# Adafruit_2_2in_TFT_HAT_rev_B.net
KiCad netlist of a schematic drawn in EAGLE
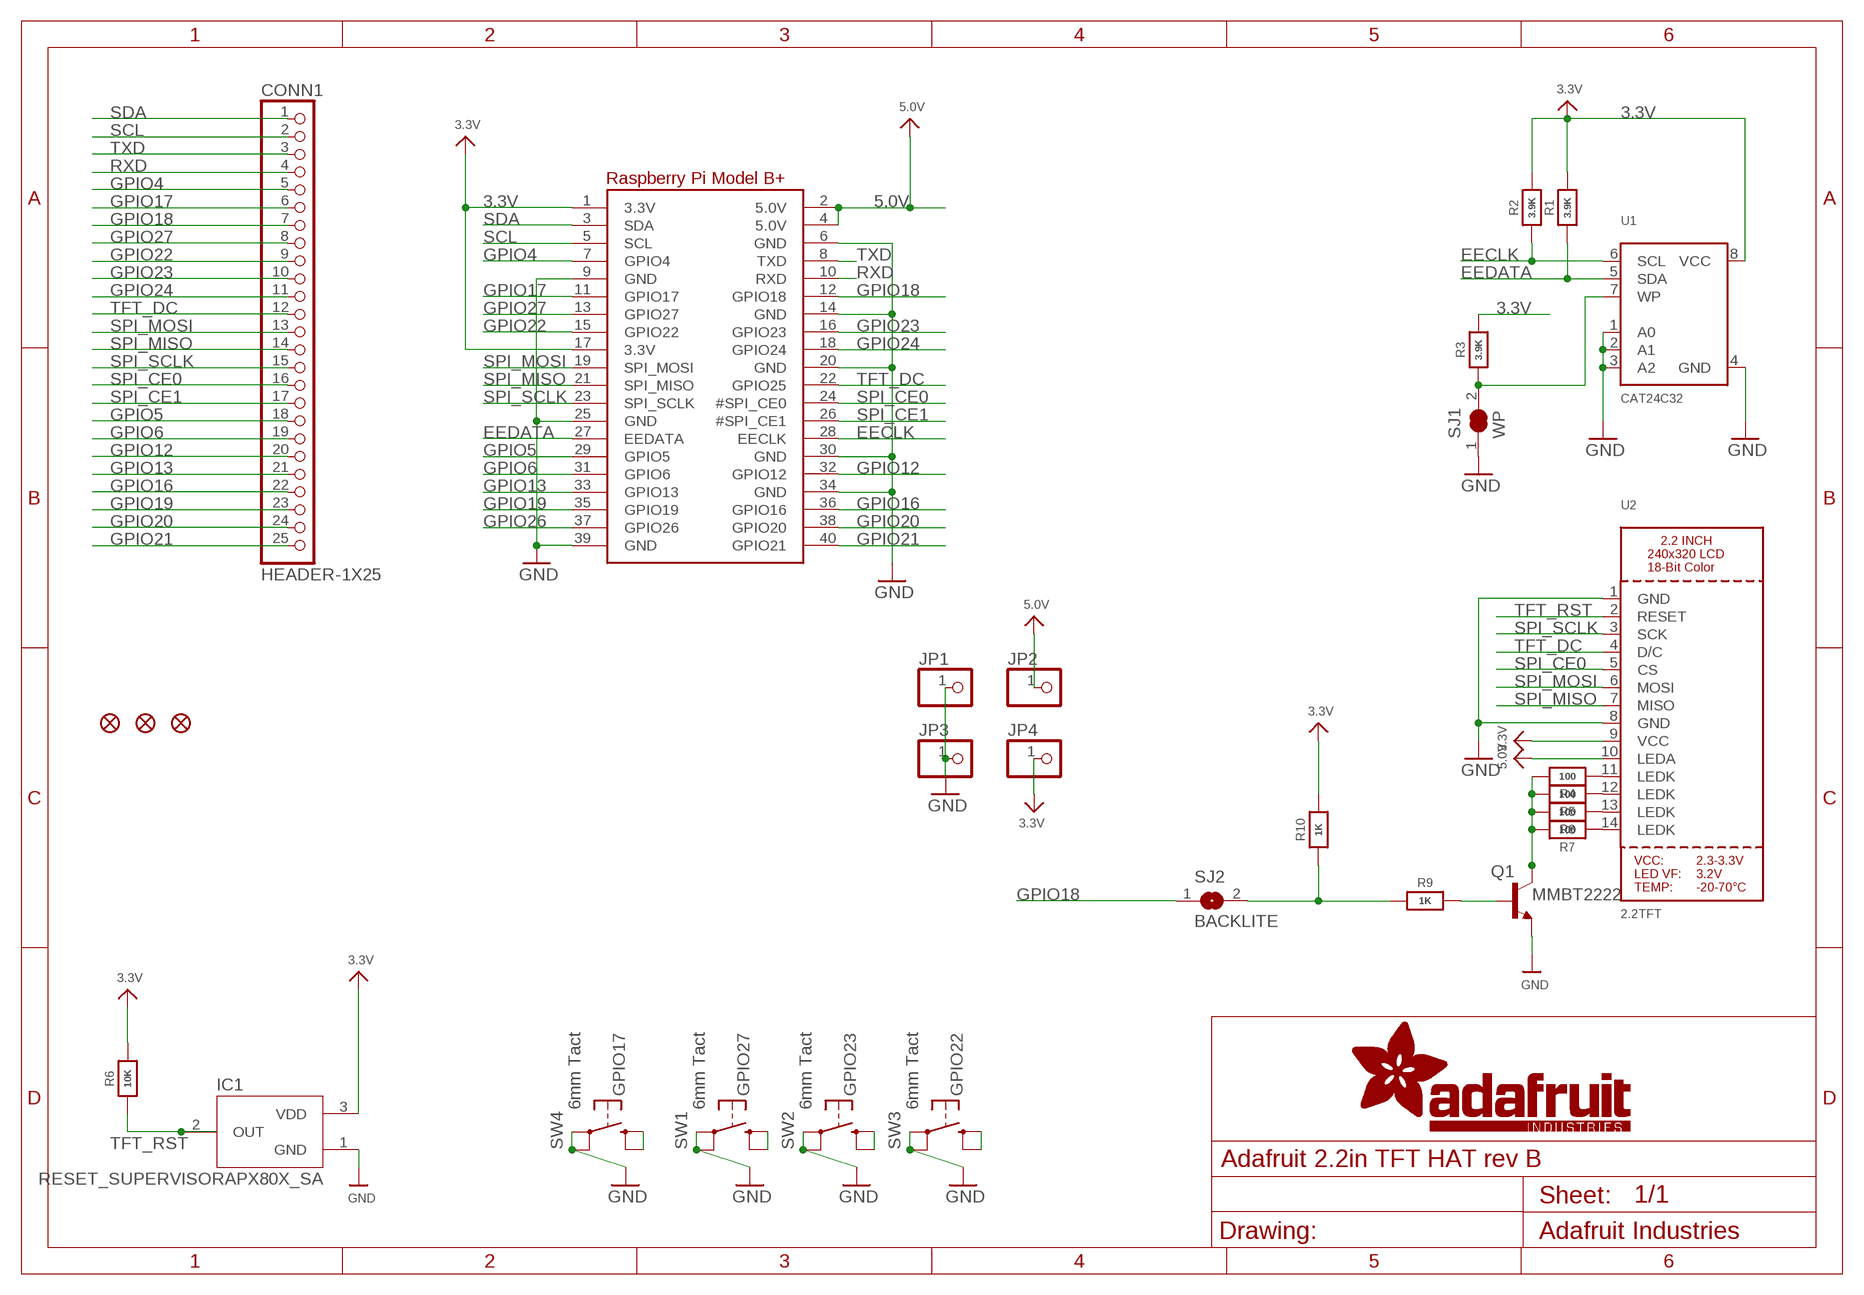
[diagram p0: schematic, sheet 1]

(export (version "E")
  (design (tool "Eeschema 10.0.6"))
  (components
    (comp (ref "CONN1")
      (value "HEADER-1X25")
      (footprint "eagle-import:1X25_ROUND_70MIL")
      (libsource (lib "eagle-import") (part "HEADER-1X25"))
    )
    (comp (ref "FID1")
      (value "FIDUCIAL_1MM")
      (footprint "eagle-import:FIDUCIAL_1MM")
      (libsource (lib "eagle-import") (part "FIDUCIAL_1MM"))
    )
    (comp (ref "FID2")
      (value "FIDUCIAL_1MM")
      (footprint "eagle-import:FIDUCIAL_1MM")
      (libsource (lib "eagle-import") (part "FIDUCIAL_1MM"))
    )
    (comp (ref "FID3")
      (value "FIDUCIAL_1MM")
      (footprint "eagle-import:FIDUCIAL_1MM")
      (libsource (lib "eagle-import") (part "FIDUCIAL_1MM"))
    )
    (comp (ref "IC1")
      (value "RESET_SUPERVISORAPX80X_SA")
      (footprint "eagle-import:SOT23-WIDE")
      (libsource (lib "eagle-import") (part "RESET_SUPERVISORAPX80X_SA"))
    )
    (comp (ref "JP1")
      (value "HEADER-1X1ROUND")
      (footprint "eagle-import:1X01_ROUND")
      (libsource (lib "eagle-import") (part "HEADER-1X1ROUND"))
    )
    (comp (ref "JP2")
      (value "HEADER-1X1ROUND")
      (footprint "eagle-import:1X01_ROUND")
      (libsource (lib "eagle-import") (part "HEADER-1X1ROUND"))
    )
    (comp (ref "JP3")
      (value "HEADER-1X1ROUND")
      (footprint "eagle-import:1X01_ROUND")
      (libsource (lib "eagle-import") (part "HEADER-1X1ROUND"))
    )
    (comp (ref "JP4")
      (value "HEADER-1X1ROUND")
      (footprint "eagle-import:1X01_ROUND")
      (libsource (lib "eagle-import") (part "HEADER-1X1ROUND"))
    )
    (comp (ref "Q1")
      (value "MMBT2222")
      (footprint "eagle-import:SOT23-BEC")
      (libsource (lib "eagle-import") (part "-NPN-SOT23-BECMMBT2222ALT1"))
    )
    (comp (ref "R1")
      (value "3.9K")
      (footprint "eagle-import:0805-NO")
      (libsource (lib "eagle-import") (part "RESISTOR0805_NOOUTLINE"))
    )
    (comp (ref "R2")
      (value "3.9K")
      (footprint "eagle-import:0805-NO")
      (libsource (lib "eagle-import") (part "RESISTOR0805_NOOUTLINE"))
    )
    (comp (ref "R3")
      (value "3.9K")
      (footprint "eagle-import:0805-NO")
      (libsource (lib "eagle-import") (part "RESISTOR0805_NOOUTLINE"))
    )
    (comp (ref "R4")
      (value "100")
      (footprint "eagle-import:0805-NO")
      (libsource (lib "eagle-import") (part "RESISTOR0805_NOOUTLINE"))
    )
    (comp (ref "R5")
      (value "100")
      (footprint "eagle-import:0805-NO")
      (libsource (lib "eagle-import") (part "RESISTOR0805_NOOUTLINE"))
    )
    (comp (ref "R6")
      (value "10K")
      (footprint "eagle-import:0805-NO")
      (libsource (lib "eagle-import") (part "RESISTOR0805_NOOUTLINE"))
    )
    (comp (ref "R7")
      (value "100")
      (footprint "eagle-import:0805-NO")
      (libsource (lib "eagle-import") (part "RESISTOR0805_NOOUTLINE"))
    )
    (comp (ref "R8")
      (value "100")
      (footprint "eagle-import:0805-NO")
      (libsource (lib "eagle-import") (part "RESISTOR0805_NOOUTLINE"))
    )
    (comp (ref "R9")
      (value "1K")
      (footprint "eagle-import:0805-NO")
      (libsource (lib "eagle-import") (part "RESISTOR0805_NOOUTLINE"))
    )
    (comp (ref "R10")
      (value "1K")
      (footprint "eagle-import:0805-NO")
      (libsource (lib "eagle-import") (part "RESISTOR0805_NOOUTLINE"))
    )
    (comp (ref "RPI1")
      (value "RASPBERRYPI_BPLUS_HATNODIM")
      (footprint "eagle-import:PI_HAT_NODIM")
      (libsource (lib "eagle-import") (part "RASPBERRYPI_BPLUS_HATNODIM"))
    )
    (comp (ref "SJ1")
      (value "WP")
      (footprint "eagle-import:SOLDERJUMPER_CLOSEDWIRE")
      (libsource (lib "eagle-import") (part "SOLDERJUMPER_CLOSED"))
    )
    (comp (ref "SJ2")
      (value "BACKLITE")
      (footprint "eagle-import:SOLDERJUMPER_CLOSEDWIRE")
      (libsource (lib "eagle-import") (part "SOLDERJUMPERCLOSED"))
    )
    (comp (ref "SW1")
      (value "6mm Tact")
      (footprint "eagle-import:EVQ-Q2")
      (libsource (lib "eagle-import") (part "SWITCH_TACT_SMT"))
    )
    (comp (ref "SW2")
      (value "6mm Tact")
      (footprint "eagle-import:EVQ-Q2")
      (libsource (lib "eagle-import") (part "SWITCH_TACT_SMT"))
    )
    (comp (ref "SW3")
      (value "6mm Tact")
      (footprint "eagle-import:EVQ-Q2")
      (libsource (lib "eagle-import") (part "SWITCH_TACT_SMT"))
    )
    (comp (ref "SW4")
      (value "6mm Tact")
      (footprint "eagle-import:EVQ-Q2")
      (libsource (lib "eagle-import") (part "SWITCH_TACT_SMT"))
    )
    (comp (ref "U1")
      (value "CAT24C32")
      (footprint "eagle-import:SOIC8_150MIL")
      (libsource (lib "eagle-import") (part "EEPROM_I2C_8PIN_GENERIC"))
    )
    (comp (ref "U2")
      (value "2.2TFT")
      (footprint "eagle-import:TM022HDH26_2.2IN_LCD")
      (libsource (lib "eagle-import") (part "DISP_LCD_TM022HDH26"))
    )
  )
  (nets
    (net (code "1") (name "/EECLK") (class "Default")
      (node (ref "R2") (pin "1") (pinfunction "1_1") (pintype "passive"))
      (node (ref "RPI1") (pin "28") (pinfunction "EECLK_28") (pintype "bidirectional"))
      (node (ref "U1") (pin "6") (pinfunction "SCL_6") (pintype "input"))
    )
    (net (code "2") (name "/EEDATA") (class "Default")
      (node (ref "R1") (pin "1") (pinfunction "1_1") (pintype "passive"))
      (node (ref "RPI1") (pin "27") (pinfunction "EEDATA_27") (pintype "bidirectional"))
      (node (ref "U1") (pin "5") (pinfunction "SDA_5") (pintype "bidirectional"))
    )
    (net (code "3") (name "/GPIO4") (class "Default")
      (node (ref "CONN1") (pin "5") (pinfunction "5_5") (pintype "passive"))
      (node (ref "RPI1") (pin "7") (pinfunction "GPIO4_7") (pintype "bidirectional"))
    )
    (net (code "4") (name "/GPIO5") (class "Default")
      (node (ref "CONN1") (pin "18") (pinfunction "18_18") (pintype "passive"))
      (node (ref "RPI1") (pin "29") (pinfunction "GPIO5_29") (pintype "bidirectional"))
    )
    (net (code "5") (name "/GPIO6") (class "Default")
      (node (ref "CONN1") (pin "19") (pinfunction "19_19") (pintype "passive"))
      (node (ref "RPI1") (pin "31") (pinfunction "GPIO6_31") (pintype "bidirectional"))
    )
    (net (code "6") (name "/GPIO12") (class "Default")
      (node (ref "CONN1") (pin "20") (pinfunction "20_20") (pintype "passive"))
      (node (ref "RPI1") (pin "32") (pinfunction "GPIO12_32") (pintype "bidirectional"))
    )
    (net (code "7") (name "/GPIO13") (class "Default")
      (node (ref "CONN1") (pin "21") (pinfunction "21_21") (pintype "passive"))
      (node (ref "RPI1") (pin "33") (pinfunction "GPIO13_33") (pintype "bidirectional"))
    )
    (net (code "8") (name "/GPIO16") (class "Default")
      (node (ref "CONN1") (pin "22") (pinfunction "22_22") (pintype "passive"))
      (node (ref "RPI1") (pin "36") (pinfunction "GPIO16_36") (pintype "bidirectional"))
    )
    (net (code "9") (name "/GPIO17") (class "Default")
      (node (ref "CONN1") (pin "6") (pinfunction "6_6") (pintype "passive"))
      (node (ref "RPI1") (pin "11") (pinfunction "GPIO17_11") (pintype "bidirectional"))
      (node (ref "SW4") (pin "B") (pinfunction "S_B") (pintype "passive"))
      (node (ref "SW4") (pin "B'") (pinfunction "S1_B'") (pintype "passive"))
    )
    (net (code "10") (name "/GPIO18") (class "Default")
      (node (ref "CONN1") (pin "7") (pinfunction "7_7") (pintype "passive"))
      (node (ref "RPI1") (pin "12") (pinfunction "GPIO18_12") (pintype "bidirectional"))
      (node (ref "SJ2") (pin "1") (pinfunction "1_1") (pintype "passive"))
    )
    (net (code "11") (name "/GPIO19") (class "Default")
      (node (ref "CONN1") (pin "23") (pinfunction "23_23") (pintype "passive"))
      (node (ref "RPI1") (pin "35") (pinfunction "GPIO19_35") (pintype "bidirectional"))
    )
    (net (code "12") (name "/GPIO20") (class "Default")
      (node (ref "CONN1") (pin "24") (pinfunction "24_24") (pintype "passive"))
      (node (ref "RPI1") (pin "38") (pinfunction "GPIO20_38") (pintype "bidirectional"))
    )
    (net (code "13") (name "/GPIO21") (class "Default")
      (node (ref "CONN1") (pin "25") (pinfunction "25_25") (pintype "passive"))
      (node (ref "RPI1") (pin "40") (pinfunction "GPIO21_40") (pintype "bidirectional"))
    )
    (net (code "14") (name "/GPIO22") (class "Default")
      (node (ref "CONN1") (pin "9") (pinfunction "9_9") (pintype "passive"))
      (node (ref "RPI1") (pin "15") (pinfunction "GPIO22_15") (pintype "bidirectional"))
      (node (ref "SW3") (pin "B") (pinfunction "S_B") (pintype "passive"))
      (node (ref "SW3") (pin "B'") (pinfunction "S1_B'") (pintype "passive"))
    )
    (net (code "15") (name "/GPIO23") (class "Default")
      (node (ref "CONN1") (pin "10") (pinfunction "10_10") (pintype "passive"))
      (node (ref "RPI1") (pin "16") (pinfunction "GPIO23_16") (pintype "bidirectional"))
      (node (ref "SW2") (pin "B") (pinfunction "S_B") (pintype "passive"))
      (node (ref "SW2") (pin "B'") (pinfunction "S1_B'") (pintype "passive"))
    )
    (net (code "16") (name "/GPIO24") (class "Default")
      (node (ref "CONN1") (pin "11") (pinfunction "11_11") (pintype "passive"))
      (node (ref "RPI1") (pin "18") (pinfunction "GPIO24_18") (pintype "bidirectional"))
    )
    (net (code "17") (name "/GPIO26") (class "Default")
      (node (ref "RPI1") (pin "37") (pinfunction "GPIO26_37") (pintype "bidirectional"))
    )
    (net (code "18") (name "/GPIO27") (class "Default")
      (node (ref "CONN1") (pin "8") (pinfunction "8_8") (pintype "passive"))
      (node (ref "RPI1") (pin "13") (pinfunction "GPIO27_13") (pintype "bidirectional"))
      (node (ref "SW1") (pin "B") (pinfunction "S_B") (pintype "passive"))
      (node (ref "SW1") (pin "B'") (pinfunction "S1_B'") (pintype "passive"))
    )
    (net (code "19") (name "/RXD") (class "Default")
      (node (ref "CONN1") (pin "4") (pinfunction "4_4") (pintype "passive"))
      (node (ref "RPI1") (pin "10") (pinfunction "RXD_10") (pintype "bidirectional"))
    )
    (net (code "20") (name "/SCL") (class "Default")
      (node (ref "CONN1") (pin "2") (pinfunction "2_2") (pintype "passive"))
      (node (ref "RPI1") (pin "5") (pinfunction "SCL_5") (pintype "bidirectional"))
    )
    (net (code "21") (name "/SDA") (class "Default")
      (node (ref "CONN1") (pin "1") (pinfunction "1_1") (pintype "passive"))
      (node (ref "RPI1") (pin "3") (pinfunction "SDA_3") (pintype "bidirectional"))
    )
    (net (code "22") (name "/SPI_CE0") (class "Default")
      (node (ref "CONN1") (pin "16") (pinfunction "16_16") (pintype "passive"))
      (node (ref "RPI1") (pin "24") (pinfunction "#SPI_CE0_24") (pintype "bidirectional"))
      (node (ref "U2") (pin "5") (pinfunction "CS_5") (pintype "input"))
    )
    (net (code "23") (name "/SPI_CE1") (class "Default")
      (node (ref "CONN1") (pin "17") (pinfunction "17_17") (pintype "passive"))
      (node (ref "RPI1") (pin "26") (pinfunction "#SPI_CE1_26") (pintype "bidirectional"))
    )
    (net (code "24") (name "/SPI_MISO") (class "Default")
      (node (ref "CONN1") (pin "14") (pinfunction "14_14") (pintype "passive"))
      (node (ref "RPI1") (pin "21") (pinfunction "SPI_MISO_21") (pintype "bidirectional"))
      (node (ref "U2") (pin "7") (pinfunction "MISO_7") (pintype "output"))
    )
    (net (code "25") (name "/SPI_MOSI") (class "Default")
      (node (ref "CONN1") (pin "13") (pinfunction "13_13") (pintype "passive"))
      (node (ref "RPI1") (pin "19") (pinfunction "SPI_MOSI_19") (pintype "bidirectional"))
      (node (ref "U2") (pin "6") (pinfunction "MOSI_6") (pintype "input"))
    )
    (net (code "26") (name "/SPI_SCLK") (class "Default")
      (node (ref "CONN1") (pin "15") (pinfunction "15_15") (pintype "passive"))
      (node (ref "RPI1") (pin "23") (pinfunction "SPI_SCLK_23") (pintype "bidirectional"))
      (node (ref "U2") (pin "3") (pinfunction "SCK_3") (pintype "input"))
    )
    (net (code "27") (name "/TFT_DC") (class "Default")
      (node (ref "CONN1") (pin "12") (pinfunction "12_12") (pintype "passive"))
      (node (ref "RPI1") (pin "22") (pinfunction "GPIO25_22") (pintype "bidirectional"))
      (node (ref "U2") (pin "4") (pinfunction "D/C_4") (pintype "input"))
    )
    (net (code "28") (name "/TFT_RST") (class "Default")
      (node (ref "IC1") (pin "2") (pinfunction "OUT_2") (pintype "output"))
      (node (ref "R6") (pin "1") (pinfunction "1_1") (pintype "passive"))
      (node (ref "U2") (pin "2") (pinfunction "RESET_2") (pintype "input"))
    )
    (net (code "29") (name "/TXD") (class "Default")
      (node (ref "CONN1") (pin "3") (pinfunction "3_3") (pintype "passive"))
      (node (ref "RPI1") (pin "8") (pinfunction "TXD_8") (pintype "bidirectional"))
    )
    (net (code "30") (name "3.3V") (class "Default")
      (node (ref "IC1") (pin "3") (pinfunction "VDD_3") (pintype "power_in"))
      (node (ref "JP4") (pin "1") (pinfunction "1_1") (pintype "passive"))
      (node (ref "R1") (pin "2") (pinfunction "2_2") (pintype "passive"))
      (node (ref "R10") (pin "2") (pinfunction "2_2") (pintype "passive"))
      (node (ref "R2") (pin "2") (pinfunction "2_2") (pintype "passive"))
      (node (ref "R3") (pin "2") (pinfunction "2_2") (pintype "passive"))
      (node (ref "R6") (pin "2") (pinfunction "2_2") (pintype "passive"))
      (node (ref "RPI1") (pin "1") (pinfunction "3.3V_1") (pintype "power_in"))
      (node (ref "RPI1") (pin "17") (pinfunction "3.3V_17") (pintype "power_in"))
      (node (ref "U1") (pin "8") (pinfunction "VCC_8") (pintype "power_in"))
      (node (ref "U2") (pin "9") (pinfunction "VCC_9") (pintype "power_in"))
    )
    (net (code "31") (name "5.0V") (class "Default")
      (node (ref "JP2") (pin "1") (pinfunction "1_1") (pintype "passive"))
      (node (ref "RPI1") (pin "2") (pinfunction "5.0V_2") (pintype "power_in"))
      (node (ref "RPI1") (pin "4") (pinfunction "5.0V_4") (pintype "power_in"))
      (node (ref "U2") (pin "10") (pinfunction "LEDA_10") (pintype "input"))
    )
    (net (code "32") (name "GND") (class "Default")
      (node (ref "IC1") (pin "1") (pinfunction "GND_1") (pintype "power_in"))
      (node (ref "JP1") (pin "1") (pinfunction "1_1") (pintype "passive"))
      (node (ref "JP3") (pin "1") (pinfunction "1_1") (pintype "passive"))
      (node (ref "Q1") (pin "E") (pinfunction "E_E") (pintype "passive"))
      (node (ref "RPI1") (pin "14") (pinfunction "GND_14") (pintype "power_in"))
      (node (ref "RPI1") (pin "20") (pinfunction "GND_20") (pintype "power_in"))
      (node (ref "RPI1") (pin "25") (pinfunction "GND_25") (pintype "power_in"))
      (node (ref "RPI1") (pin "30") (pinfunction "GND_30") (pintype "power_in"))
      (node (ref "RPI1") (pin "34") (pinfunction "GND_34") (pintype "power_in"))
      (node (ref "RPI1") (pin "39") (pinfunction "GND_39") (pintype "power_in"))
      (node (ref "RPI1") (pin "6") (pinfunction "GND_6") (pintype "power_in"))
      (node (ref "RPI1") (pin "9") (pinfunction "GND_9") (pintype "power_in"))
      (node (ref "SJ1") (pin "1") (pinfunction "1_1") (pintype "passive"))
      (node (ref "SW1") (pin "A") (pinfunction "P_A") (pintype "passive"))
      (node (ref "SW1") (pin "A'") (pinfunction "P1_A'") (pintype "passive"))
      (node (ref "SW2") (pin "A") (pinfunction "P_A") (pintype "passive"))
      (node (ref "SW2") (pin "A'") (pinfunction "P1_A'") (pintype "passive"))
      (node (ref "SW3") (pin "A") (pinfunction "P_A") (pintype "passive"))
      (node (ref "SW3") (pin "A'") (pinfunction "P1_A'") (pintype "passive"))
      (node (ref "SW4") (pin "A") (pinfunction "P_A") (pintype "passive"))
      (node (ref "SW4") (pin "A'") (pinfunction "P1_A'") (pintype "passive"))
      (node (ref "U1") (pin "1") (pinfunction "A0_1") (pintype "input"))
      (node (ref "U1") (pin "2") (pinfunction "A1_2") (pintype "input"))
      (node (ref "U1") (pin "3") (pinfunction "A2_3") (pintype "input"))
      (node (ref "U1") (pin "4") (pinfunction "GND_4") (pintype "power_in"))
      (node (ref "U2") (pin "1") (pinfunction "GND_1") (pintype "power_in"))
      (node (ref "U2") (pin "8") (pinfunction "GND_8") (pintype "power_in"))
    )
    (net (code "33") (name "Net-(Q1-PadB)") (class "Default")
      (node (ref "Q1") (pin "B") (pinfunction "B_B") (pintype "passive"))
      (node (ref "R9") (pin "2") (pinfunction "2_2") (pintype "passive"))
    )
    (net (code "34") (name "Net-(Q1-PadC)") (class "Default")
      (node (ref "Q1") (pin "C") (pinfunction "C_C") (pintype "passive"))
      (node (ref "R4") (pin "2") (pinfunction "2_2") (pintype "passive"))
      (node (ref "R5") (pin "2") (pinfunction "2_2") (pintype "passive"))
      (node (ref "R7") (pin "2") (pinfunction "2_2") (pintype "passive"))
      (node (ref "R8") (pin "2") (pinfunction "2_2") (pintype "passive"))
    )
    (net (code "35") (name "Net-(R4-Pad1)") (class "Default")
      (node (ref "R4") (pin "1") (pinfunction "1_1") (pintype "passive"))
      (node (ref "U2") (pin "11") (pinfunction "LEDK_11") (pintype "input"))
    )
    (net (code "36") (name "Net-(R5-Pad1)") (class "Default")
      (node (ref "R5") (pin "1") (pinfunction "1_1") (pintype "passive"))
      (node (ref "U2") (pin "12") (pinfunction "LEDK_12") (pintype "input"))
    )
    (net (code "37") (name "Net-(R7-Pad1)") (class "Default")
      (node (ref "R7") (pin "1") (pinfunction "1_1") (pintype "passive"))
      (node (ref "U2") (pin "14") (pinfunction "LEDK_14") (pintype "input"))
    )
    (net (code "38") (name "Net-(R8-Pad1)") (class "Default")
      (node (ref "R8") (pin "1") (pinfunction "1_1") (pintype "passive"))
      (node (ref "U2") (pin "13") (pinfunction "LEDK_13") (pintype "input"))
    )
    (net (code "39") (name "Net-(R10-Pad1)") (class "Default")
      (node (ref "R10") (pin "1") (pinfunction "1_1") (pintype "passive"))
      (node (ref "R9") (pin "1") (pinfunction "1_1") (pintype "passive"))
      (node (ref "SJ2") (pin "2") (pinfunction "2_2") (pintype "passive"))
    )
    (net (code "40") (name "Net-(U1-WP)") (class "Default")
      (node (ref "R3") (pin "1") (pinfunction "1_1") (pintype "passive"))
      (node (ref "SJ1") (pin "2") (pinfunction "2_2") (pintype "passive"))
      (node (ref "U1") (pin "7") (pinfunction "WP_7") (pintype "input"))
    )
  )
)
